# OpenPLCv0_2_0_Display.net
KiCad netlist of a schematic drawn in Altium Designer
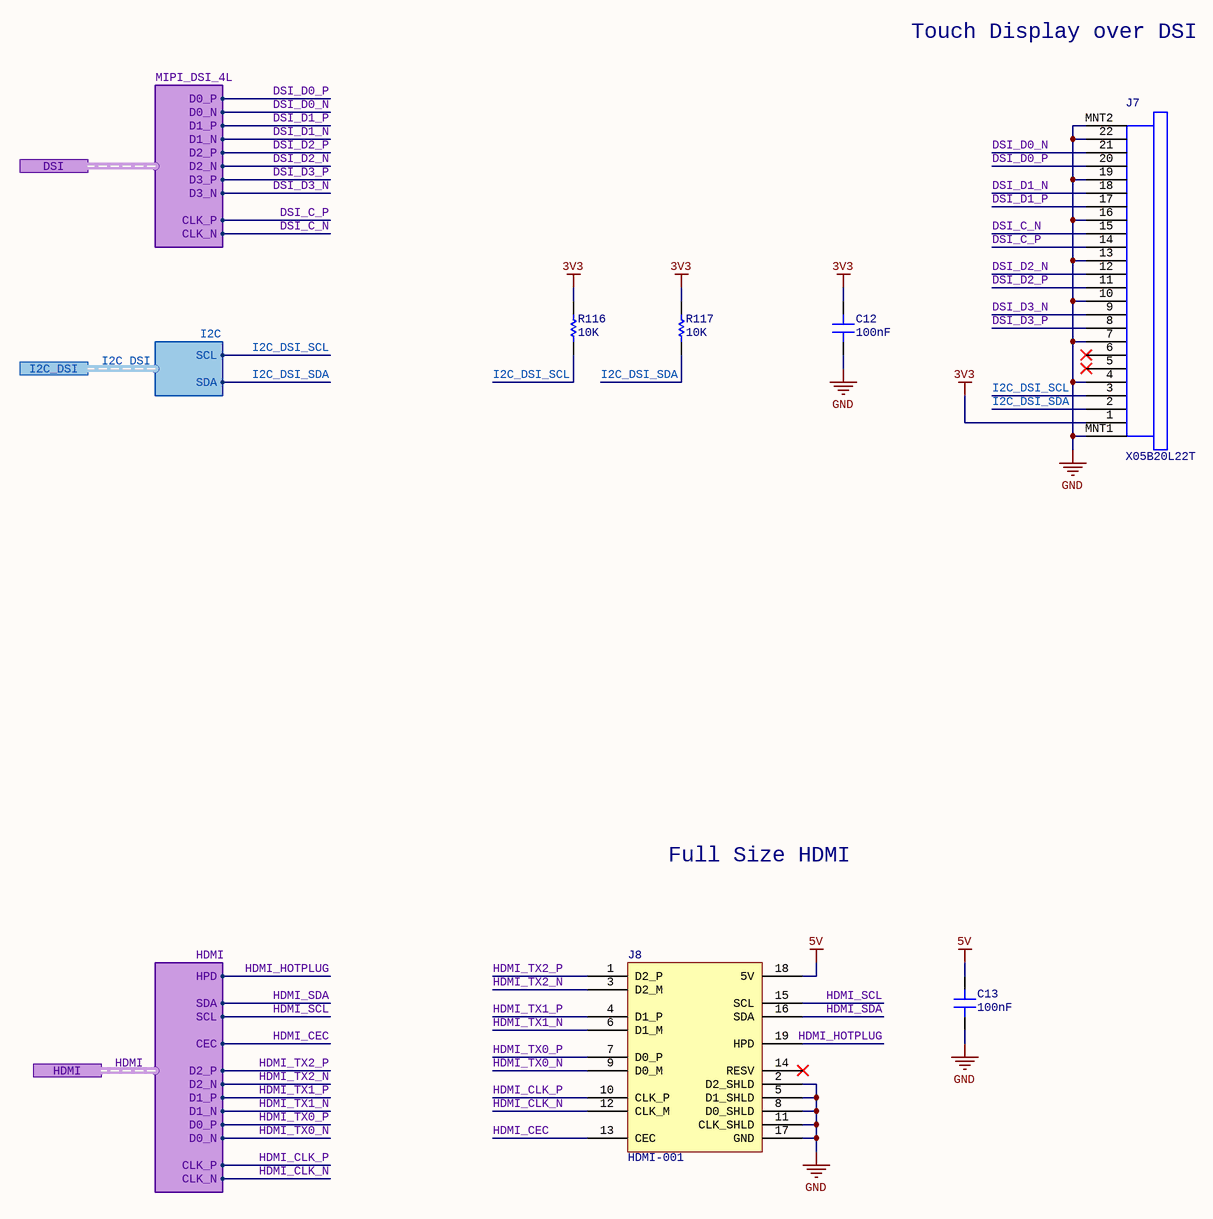
[diagram p0: OpenPLCv0.2.0_Display.SchDoc]

(export (version "E")
  (design (tool "Eeschema 10.0.6"))
  (components
    (comp (ref "C12")
      (value "CC0402KRX5R6BB104")
      (footprint "SMD_CAP_0402(1005)_N")
      (description "100nF ±10% 10V X5R 0402 Multilayer Ceramic Capacitors MLCC - SMD/SMT RoHS")
      (fields (field (name "TOLERANCE") "10%") (field (name "CAPACITANCE") "100nF"))
      (libsource (lib "BrauV2_Capacitor") (part "100nF 0402 10V 10%"))
    )
    (comp (ref "C13")
      (value "CC0402KRX5R6BB104")
      (footprint "SMD_CAP_0402(1005)_N")
      (description "100nF ±10% 10V X5R 0402 Multilayer Ceramic Capacitors MLCC - SMD/SMT RoHS")
      (fields (field (name "TOLERANCE") "10%") (field (name "CAPACITANCE") "100nF"))
      (libsource (lib "BrauV2_Capacitor") (part "100nF 0402 10V 10%"))
    )
    (comp (ref "J7")
      (value "X05B20L22T")
      (footprint "X05B20L22T")
      (description "22 0.020\"（0.50mm） 0.079\"（2.00mm） Slide Lock Contact,Bottom SMD,P=0.5mm FFC, FPC Connectors ROHS")
      (libsource (lib "OpenPLCv0.2.0_Connector") (part "X05B20L22T"))
    )
    (comp (ref "J8")
      (value "HDMI-001")
      (footprint "HDMI-001")
      (description "BOOMELE(Boom Precision Elec) HDMIconnector 19 Female Horizontal SMD Audio & Video Connectors RoHS")
      (libsource (lib "BrauV2_Connector") (part "HDMI-001"))
    )
    (comp (ref "R116")
      (value "RC0402FR-0710KL")
      (footprint "SMD_RES_0402(1005)_N")
      (description "10kΩ ±1% 1/16W ±100ppm/℃ 0402 Chip Resistor - Surface Mount RoHS")
      (fields (field (name "TOLERANCE") "1%") (field (name "RESISTANCE") "10K"))
      (libsource (lib "BrauV2_Resistor") (part "10K 0402 1% 1/16W"))
    )
    (comp (ref "R117")
      (value "RC0402FR-0710KL")
      (footprint "SMD_RES_0402(1005)_N")
      (description "10kΩ ±1% 1/16W ±100ppm/℃ 0402 Chip Resistor - Surface Mount RoHS")
      (fields (field (name "TOLERANCE") "1%") (field (name "RESISTANCE") "10K"))
      (libsource (lib "BrauV2_Resistor") (part "10K 0402 1% 1/16W"))
    )
  )
  (nets
    (net (code "4") (name "/DSI_C_N") (class "Default")
      (node (ref "J7") (pin "15") (pinfunction "15_15") (pintype "passive"))
    )
    (net (code "5") (name "/DSI_C_P") (class "Default")
      (node (ref "J7") (pin "14") (pinfunction "14_14") (pintype "passive"))
    )
    (net (code "6") (name "/DSI_D0_N") (class "Default")
      (node (ref "J7") (pin "21") (pinfunction "21_21") (pintype "passive"))
    )
    (net (code "7") (name "/DSI_D0_P") (class "Default")
      (node (ref "J7") (pin "20") (pinfunction "20_20") (pintype "passive"))
    )
    (net (code "8") (name "/DSI_D1_N") (class "Default")
      (node (ref "J7") (pin "18") (pinfunction "18_18") (pintype "passive"))
    )
    (net (code "9") (name "/DSI_D1_P") (class "Default")
      (node (ref "J7") (pin "17") (pinfunction "17_17") (pintype "passive"))
    )
    (net (code "10") (name "/DSI_D2_N") (class "Default")
      (node (ref "J7") (pin "12") (pinfunction "12_12") (pintype "passive"))
    )
    (net (code "11") (name "/DSI_D2_P") (class "Default")
      (node (ref "J7") (pin "11") (pinfunction "11_11") (pintype "passive"))
    )
    (net (code "12") (name "/DSI_D3_N") (class "Default")
      (node (ref "J7") (pin "9") (pinfunction "9_9") (pintype "passive"))
    )
    (net (code "13") (name "/DSI_D3_P") (class "Default")
      (node (ref "J7") (pin "8") (pinfunction "8_8") (pintype "passive"))
    )
    (net (code "14") (name "/HDMI_CEC") (class "Default")
      (node (ref "J8") (pin "13") (pinfunction "CEC_13") (pintype "passive"))
    )
    (net (code "15") (name "/HDMI_CLK_N") (class "Default")
      (node (ref "J8") (pin "12") (pinfunction "CLK_M_12") (pintype "passive"))
    )
    (net (code "16") (name "/HDMI_CLK_P") (class "Default")
      (node (ref "J8") (pin "10") (pinfunction "CLK_P_10") (pintype "passive"))
    )
    (net (code "17") (name "/HDMI_HOTPLUG") (class "Default")
      (node (ref "J8") (pin "19") (pinfunction "HPD_19") (pintype "passive"))
    )
    (net (code "18") (name "/HDMI_SCL") (class "Default")
      (node (ref "J8") (pin "15") (pinfunction "SCL_15") (pintype "passive"))
    )
    (net (code "19") (name "/HDMI_SDA") (class "Default")
      (node (ref "J8") (pin "16") (pinfunction "SDA_16") (pintype "passive"))
    )
    (net (code "20") (name "/HDMI_TX0_N") (class "Default")
      (node (ref "J8") (pin "9") (pinfunction "D0_M_9") (pintype "passive"))
    )
    (net (code "21") (name "/HDMI_TX0_P") (class "Default")
      (node (ref "J8") (pin "7") (pinfunction "D0_P_7") (pintype "passive"))
    )
    (net (code "22") (name "/HDMI_TX1_N") (class "Default")
      (node (ref "J8") (pin "6") (pinfunction "D1_M_6") (pintype "passive"))
    )
    (net (code "23") (name "/HDMI_TX1_P") (class "Default")
      (node (ref "J8") (pin "4") (pinfunction "D1_P_4") (pintype "passive"))
    )
    (net (code "24") (name "/HDMI_TX2_N") (class "Default")
      (node (ref "J8") (pin "3") (pinfunction "D2_M_3") (pintype "passive"))
    )
    (net (code "25") (name "/HDMI_TX2_P") (class "Default")
      (node (ref "J8") (pin "1") (pinfunction "D2_P_1") (pintype "passive"))
    )
    (net (code "27") (name "/I2C_DSI_SCL") (class "Default")
      (node (ref "J7") (pin "3") (pinfunction "3_3") (pintype "passive"))
      (node (ref "R116") (pin "1") (pinfunction "1_1") (pintype "passive"))
    )
    (net (code "28") (name "/I2C_DSI_SDA") (class "Default")
      (node (ref "J7") (pin "2") (pinfunction "2_2") (pintype "passive"))
      (node (ref "R117") (pin "1") (pinfunction "1_1") (pintype "passive"))
    )
    (net (code "31") (name "3V3") (class "Default")
      (node (ref "C12") (pin "2") (pinfunction "2_2") (pintype "passive"))
      (node (ref "J7") (pin "1") (pinfunction "1_1") (pintype "passive"))
      (node (ref "R116") (pin "2") (pinfunction "2_2") (pintype "passive"))
      (node (ref "R117") (pin "2") (pinfunction "2_2") (pintype "passive"))
    )
    (net (code "32") (name "5V") (class "Default")
      (node (ref "C13") (pin "2") (pinfunction "2_2") (pintype "passive"))
      (node (ref "J8") (pin "18") (pinfunction "5V_18") (pintype "passive"))
    )
    (net (code "33") (name "GND") (class "Default")
      (node (ref "C12") (pin "1") (pinfunction "1_1") (pintype "passive"))
      (node (ref "C13") (pin "1") (pinfunction "1_1") (pintype "passive"))
      (node (ref "J7") (pin "10") (pinfunction "10_10") (pintype "passive"))
      (node (ref "J7") (pin "13") (pinfunction "13_13") (pintype "passive"))
      (node (ref "J7") (pin "16") (pinfunction "16_16") (pintype "passive"))
      (node (ref "J7") (pin "19") (pinfunction "19_19") (pintype "passive"))
      (node (ref "J7") (pin "22") (pinfunction "22_22") (pintype "passive"))
      (node (ref "J7") (pin "4") (pinfunction "4_4") (pintype "passive"))
      (node (ref "J7") (pin "7") (pinfunction "7_7") (pintype "passive"))
      (node (ref "J7") (pin "MNT1") (pinfunction "MNT1_MNT1") (pintype "passive"))
      (node (ref "J7") (pin "MNT2") (pinfunction "MNT2_MNT2") (pintype "passive"))
      (node (ref "J8") (pin "11") (pinfunction "CLK_SHLD_11") (pintype "passive"))
      (node (ref "J8") (pin "17") (pinfunction "GND_17") (pintype "passive"))
      (node (ref "J8") (pin "2") (pinfunction "D2_SHLD_2") (pintype "passive"))
      (node (ref "J8") (pin "5") (pinfunction "D1_SHLD_5") (pintype "passive"))
      (node (ref "J8") (pin "8") (pinfunction "D0_SHLD_8") (pintype "passive"))
    )
    (net (code "34") (name "unconnected-(J7-Pad5)") (class "Default")
      (node (ref "J7") (pin "5") (pinfunction "5_5") (pintype "passive+no_connect"))
    )
    (net (code "35") (name "unconnected-(J7-Pad6)") (class "Default")
      (node (ref "J7") (pin "6") (pinfunction "6_6") (pintype "passive+no_connect"))
    )
    (net (code "36") (name "unconnected-(J8-RESV-Pad14)") (class "Default")
      (node (ref "J8") (pin "14") (pinfunction "RESV_14") (pintype "passive+no_connect"))
    )
  )
)
